# SD.net
KiCad netlist of a schematic drawn in Altium Designer
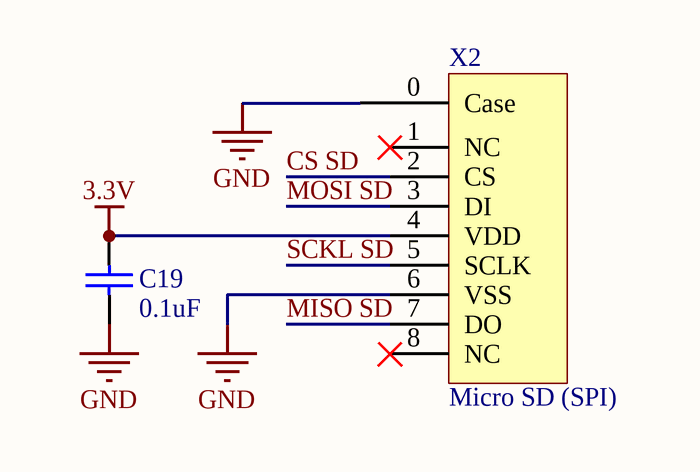
[diagram p0: SD.SchDoc]

(export (version "E")
  (design (tool "Eeschema 10.0.6"))
  (components
    (comp (ref "C19")
      (value "0.1uF")
      (footprint "Capacitors:C0603")
      (description "0.1uF ceramic capacitor")
      (fields (field (name "MANUFACTURER") "TDK Corporation") (field (name "TOLERANCE") "10%"))
      (libsource (lib "Capacitors") (part "CAP CER 0603 0.1uF 50V C0G 10%"))
    )
    (comp (ref "X2")
      (value "Micro SD (SPI)")
      (footprint "475710001")
      (description "microSD connector, Surface Mount, Right Angle")
      (fields (field (name "MANUFACTURER") "Molex") (field (name "PART_NUMBER") "47571-0001"))
      (libsource (lib "Other") (part "475710001"))
    )
  )
  (nets
    (net (code "1") (name "/CS SD") (class "Default")
      (node (ref "X2") (pin "2") (pinfunction "CS_2") (pintype "passive"))
    )
    (net (code "2") (name "/MISO SD") (class "Default")
      (node (ref "X2") (pin "7") (pinfunction "DO_7") (pintype "passive"))
    )
    (net (code "3") (name "/MOSI SD") (class "Default")
      (node (ref "X2") (pin "3") (pinfunction "DI_3") (pintype "passive"))
    )
    (net (code "4") (name "/SCKL SD") (class "Default")
      (node (ref "X2") (pin "5") (pinfunction "SCLK_5") (pintype "passive"))
    )
    (net (code "5") (name "3.3V") (class "Default")
      (node (ref "C19") (pin "2") (pinfunction "2_2") (pintype "passive"))
      (node (ref "X2") (pin "4") (pinfunction "VDD_4") (pintype "passive"))
    )
    (net (code "6") (name "GND") (class "Default")
      (node (ref "C19") (pin "1") (pinfunction "1_1") (pintype "passive"))
      (node (ref "X2") (pin "0") (pinfunction "Case_0") (pintype "passive"))
      (node (ref "X2") (pin "6") (pinfunction "VSS_6") (pintype "passive"))
    )
    (net (code "7") (name "unconnected-(X2-NC-Pad1)") (class "Default")
      (node (ref "X2") (pin "1") (pinfunction "NC_1") (pintype "passive+no_connect"))
    )
    (net (code "8") (name "unconnected-(X2-NC-Pad8)") (class "Default")
      (node (ref "X2") (pin "8") (pinfunction "NC_8") (pintype "passive+no_connect"))
    )
  )
)
